# Switch_PCB_Schematic.net
KiCad netlist of a schematic drawn in Altium Designer
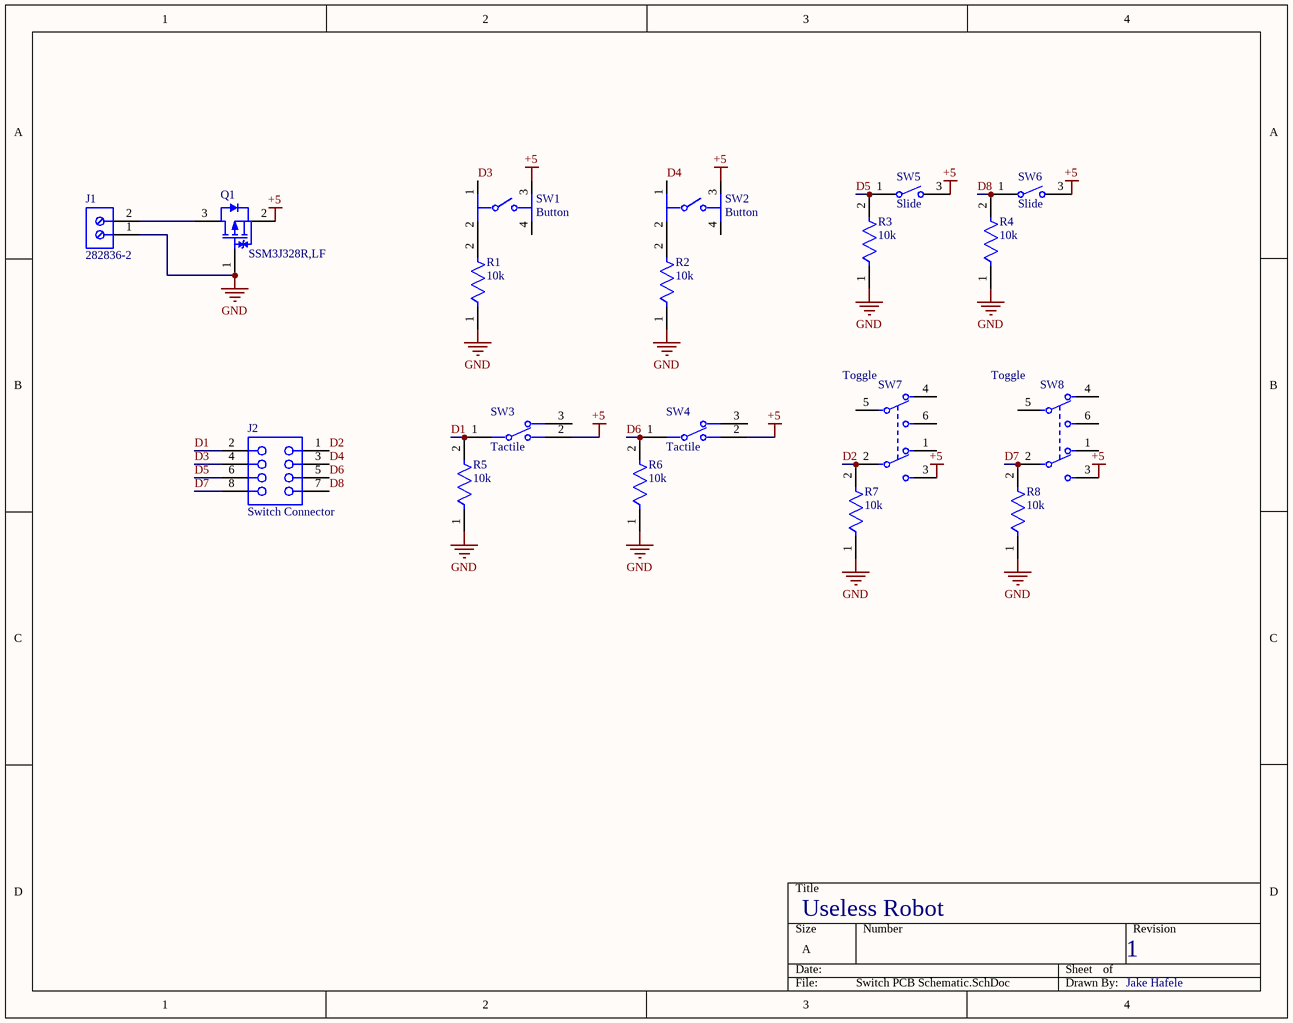
[diagram p0: Switch PCB Schematic.SchDoc]

(export (version "E")
  (design (tool "Eeschema 10.0.6"))
  (components
    (comp (ref "J1")
      (value "282836-2")
      (footprint "TECO-282836-2_V")
      (description "Female Header, Pitch 5 mm, 1 x 2 Position, Height 10 mm, Tail Length 3.5 mm, Rohs, Bulk")
      (fields (field (name "VOLTAGE") "300V") (field (name "MANUFACTURER") "TE Connectivity"))
      (libsource (lib "Altium Content Vault") (part "CN-1P-F-TB2"))
    )
    (comp (ref "J2")
      (value "Switch Connector")
      (footprint "SMTC-SSW-104-01-X-D")
      (description "SQ Post Socket, Through-hole, Vertical, -55 to 105 degC, 2.54mm Pitch, 8-Pin, Female, RoHS")
      (fields (field (name "PARTNUMBER") "SSW-104-01-T-D") (field (name "MANUFACTURER") "Samtec"))
      (libsource (lib "Altium Content Vault") (part "SMTC-SSW-104-X-X-D"))
    )
    (comp (ref "Q1")
      (value "SSM3J328R,LF")
      (footprint "TOSH-SOT-23F_V")
      (fields (field (name "MANUFACTURER") "Toshiba"))
      (libsource (lib "Altium Content Vault") (part "PEMOS-GSD-3_C"))
    )
    (comp (ref "R1")
      (value "10k")
      (footprint "FP-RT1206-MFG")
      (description "RES SMD 10K OHM 0.5% 1/4W 1206")
      (fields (field (name "MANUFACTURER PART NUMBER") "RT1206DRE0710KL") (field (name "TOLERANCE") "0.0001"))
      (libsource (lib "Altium Content Vault") (part "1029c3af85768c4190bb7ad29bc67b5"))
    )
    (comp (ref "R2")
      (value "10k")
      (footprint "FP-RT1206-MFG")
      (description "RES SMD 10K OHM 0.5% 1/4W 1206")
      (fields (field (name "MANUFACTURER PART NUMBER") "RT1206DRE0710KL") (field (name "TOLERANCE") "0.0001"))
      (libsource (lib "Altium Content Vault") (part "1029c3af85768c4190bb7ad29bc67b5"))
    )
    (comp (ref "R3")
      (value "10k")
      (footprint "FP-RT1206-MFG")
      (description "RES SMD 10K OHM 0.5% 1/4W 1206")
      (fields (field (name "MANUFACTURER PART NUMBER") "RT1206DRE0710KL") (field (name "TOLERANCE") "0.0001"))
      (libsource (lib "Altium Content Vault") (part "1029c3af85768c4190bb7ad29bc67b5"))
    )
    (comp (ref "R4")
      (value "10k")
      (footprint "FP-RT1206-MFG")
      (description "RES SMD 10K OHM 0.5% 1/4W 1206")
      (fields (field (name "MANUFACTURER PART NUMBER") "RT1206DRE0710KL") (field (name "TOLERANCE") "0.0001"))
      (libsource (lib "Altium Content Vault") (part "1029c3af85768c4190bb7ad29bc67b5"))
    )
    (comp (ref "R5")
      (value "10k")
      (footprint "FP-RT1206-MFG")
      (description "RES SMD 10K OHM 0.5% 1/4W 1206")
      (fields (field (name "MANUFACTURER PART NUMBER") "RT1206DRE0710KL") (field (name "TOLERANCE") "0.0001"))
      (libsource (lib "Altium Content Vault") (part "1029c3af85768c4190bb7ad29bc67b5"))
    )
    (comp (ref "R6")
      (value "10k")
      (footprint "FP-RT1206-MFG")
      (description "RES SMD 10K OHM 0.5% 1/4W 1206")
      (fields (field (name "MANUFACTURER PART NUMBER") "RT1206DRE0710KL") (field (name "TOLERANCE") "0.0001"))
      (libsource (lib "Altium Content Vault") (part "1029c3af85768c4190bb7ad29bc67b5"))
    )
    (comp (ref "R7")
      (value "10k")
      (footprint "FP-RT1206-MFG")
      (description "RES SMD 10K OHM 0.5% 1/4W 1206")
      (fields (field (name "MANUFACTURER PART NUMBER") "RT1206DRE0710KL") (field (name "TOLERANCE") "0.0001"))
      (libsource (lib "Altium Content Vault") (part "1029c3af85768c4190bb7ad29bc67b5"))
    )
    (comp (ref "R8")
      (value "10k")
      (footprint "FP-RT1206-MFG")
      (description "RES SMD 10K OHM 0.5% 1/4W 1206")
      (fields (field (name "MANUFACTURER PART NUMBER") "RT1206DRE0710KL") (field (name "TOLERANCE") "0.0001"))
      (libsource (lib "Altium Content Vault") (part "1029c3af85768c4190bb7ad29bc67b5"))
    )
    (comp (ref "SW1")
      (value "Button")
      (footprint "FP-1825910-2-0")
      (description "SWITCH TACTILE SPST-NO 0.05A 24V. Push button")
      (fields
        (field (name "OCTOPART") "https://octopart.com/1825910-2-te+connectivity-42270502")
        (field (name "MANUFACTURER") "TE")
      )
      (libsource (lib "Altium Content Vault") (part "b8895f3f4cefb76e1819d2863dba89b"))
    )
    (comp (ref "SW2")
      (value "Button")
      (footprint "FP-1825910-2-0")
      (description "SWITCH TACTILE SPST-NO 0.05A 24V. Push button")
      (fields
        (field (name "OCTOPART") "https://octopart.com/1825910-2-te+connectivity-42270502")
        (field (name "MANUFACTURER") "TE")
      )
      (libsource (lib "Altium Content Vault") (part "b8895f3f4cefb76e1819d2863dba89b"))
    )
    (comp (ref "SW3")
      (value "Tactile")
      (footprint "FP-SS-5GL2D-MFG")
      (description "SWITCH SNAP ACTION SPDT 5A 125V. Snap Action")
      (libsource (lib "Altium Content Vault") (part "2590abc66e99d69838a2e17c76decd2"))
    )
    (comp (ref "SW4")
      (value "Tactile")
      (footprint "FP-SS-5GL2D-MFG")
      (description "SWITCH SNAP ACTION SPDT 5A 125V. Snap Action")
      (libsource (lib "Altium Content Vault") (part "2590abc66e99d69838a2e17c76decd2"))
    )
    (comp (ref "SW5")
      (value "Slide")
      (footprint "CKCP-TS02CBE_V")
      (description "Tiny Slide Switch, SPST, 20 V, -30 to 85 degC, 2-Pin THD, RoHS, Bulk Slide Switch")
      (fields (field (name "MANUFACTURER") "C&K Components"))
      (libsource (lib "Altium Content Vault") (part "SW-SPST-2"))
    )
    (comp (ref "SW6")
      (value "Slide")
      (footprint "CKCP-TS02CBE_V")
      (description "Tiny Slide Switch, SPST, 20 V, -30 to 85 degC, 2-Pin THD, RoHS, Bulk Slide Switch")
      (fields (field (name "MANUFACTURER") "C&K Components"))
      (libsource (lib "Altium Content Vault") (part "SW-SPST-2"))
    )
    (comp (ref "SW7")
      (value "Toggle")
      (footprint "FP-100DP1T2B3M2QEH-MFG")
      (description "SWITCH TOGGLE NON ILLUMINATED. Double Pole Single Throw")
      (fields
        (field (name "MANUFACTURER") "E-Switch")
        (field (name "OCTOPART") "https://octopart.com/100dp1t2b3m2qeh-e-switch-7054946")
      )
      (libsource (lib "Altium Content Vault") (part "0cfc74b8a78428f8f812a73d8c28120"))
    )
    (comp (ref "SW8")
      (value "Toggle")
      (footprint "FP-100DP1T2B3M2QEH-MFG")
      (description "SWITCH TOGGLE NON ILLUMINATED. Double Pole Single Throw")
      (fields
        (field (name "MANUFACTURER") "E-Switch")
        (field (name "OCTOPART") "https://octopart.com/100dp1t2b3m2qeh-e-switch-7054946")
      )
      (libsource (lib "Altium Content Vault") (part "0cfc74b8a78428f8f812a73d8c28120"))
    )
  )
  (nets
    (net (code "1") (name "+5") (class "Default")
      (node (ref "Q1") (pin "2") (pinfunction "S_2") (pintype "passive"))
      (node (ref "SW1") (pin "3") (pinfunction "3_3") (pintype "passive"))
      (node (ref "SW2") (pin "3") (pinfunction "3_3") (pintype "passive"))
      (node (ref "SW3") (pin "2") (pinfunction "NO_2") (pintype "passive"))
      (node (ref "SW4") (pin "2") (pinfunction "NO_2") (pintype "passive"))
      (node (ref "SW5") (pin "3") (pinfunction "3_3") (pintype "passive"))
      (node (ref "SW6") (pin "3") (pinfunction "3_3") (pintype "passive"))
      (node (ref "SW7") (pin "3") (pinfunction "3_3") (pintype "passive"))
      (node (ref "SW8") (pin "3") (pinfunction "3_3") (pintype "passive"))
    )
    (net (code "2") (name "/D1") (class "Default")
      (node (ref "J2") (pin "2") (pinfunction "2_2") (pintype "passive"))
      (node (ref "R5") (pin "2") (pinfunction "2_2") (pintype "passive"))
      (node (ref "SW3") (pin "1") (pinfunction "COM_1") (pintype "passive"))
    )
    (net (code "3") (name "/D2") (class "Default")
      (node (ref "J2") (pin "1") (pinfunction "1_1") (pintype "passive"))
      (node (ref "R7") (pin "2") (pinfunction "2_2") (pintype "passive"))
      (node (ref "SW7") (pin "2") (pinfunction "2_2") (pintype "passive"))
    )
    (net (code "4") (name "/D3") (class "Default")
      (node (ref "J2") (pin "4") (pinfunction "4_4") (pintype "passive"))
      (node (ref "SW1") (pin "1") (pinfunction "1_1") (pintype "passive"))
    )
    (net (code "5") (name "/D4") (class "Default")
      (node (ref "J2") (pin "3") (pinfunction "3_3") (pintype "passive"))
      (node (ref "SW2") (pin "1") (pinfunction "1_1") (pintype "passive"))
    )
    (net (code "6") (name "/D5") (class "Default")
      (node (ref "J2") (pin "6") (pinfunction "6_6") (pintype "passive"))
      (node (ref "R3") (pin "2") (pinfunction "2_2") (pintype "passive"))
      (node (ref "SW5") (pin "1") (pinfunction "1_1") (pintype "passive"))
    )
    (net (code "7") (name "/D6") (class "Default")
      (node (ref "J2") (pin "5") (pinfunction "5_5") (pintype "passive"))
      (node (ref "R6") (pin "2") (pinfunction "2_2") (pintype "passive"))
      (node (ref "SW4") (pin "1") (pinfunction "COM_1") (pintype "passive"))
    )
    (net (code "8") (name "/D7") (class "Default")
      (node (ref "J2") (pin "8") (pinfunction "8_8") (pintype "passive"))
      (node (ref "R8") (pin "2") (pinfunction "2_2") (pintype "passive"))
      (node (ref "SW8") (pin "2") (pinfunction "2_2") (pintype "passive"))
    )
    (net (code "9") (name "/D8") (class "Default")
      (node (ref "J2") (pin "7") (pinfunction "7_7") (pintype "passive"))
      (node (ref "R4") (pin "2") (pinfunction "2_2") (pintype "passive"))
      (node (ref "SW6") (pin "1") (pinfunction "1_1") (pintype "passive"))
    )
    (net (code "10") (name "GND") (class "Default")
      (node (ref "J1") (pin "1") (pinfunction "1_1") (pintype "passive"))
      (node (ref "Q1") (pin "1") (pinfunction "G_1") (pintype "passive"))
      (node (ref "R1") (pin "1") (pinfunction "1_1") (pintype "passive"))
      (node (ref "R2") (pin "1") (pinfunction "1_1") (pintype "passive"))
      (node (ref "R3") (pin "1") (pinfunction "1_1") (pintype "passive"))
      (node (ref "R4") (pin "1") (pinfunction "1_1") (pintype "passive"))
      (node (ref "R5") (pin "1") (pinfunction "1_1") (pintype "passive"))
      (node (ref "R6") (pin "1") (pinfunction "1_1") (pintype "passive"))
      (node (ref "R7") (pin "1") (pinfunction "1_1") (pintype "passive"))
      (node (ref "R8") (pin "1") (pinfunction "1_1") (pintype "passive"))
    )
    (net (code "11") (name "Net-(Q1-D)") (class "Default")
      (node (ref "J1") (pin "2") (pinfunction "2_2") (pintype "passive"))
      (node (ref "Q1") (pin "3") (pinfunction "D_3") (pintype "passive"))
    )
    (net (code "12") (name "Net-(R1-Pad2)") (class "Default")
      (node (ref "R1") (pin "2") (pinfunction "2_2") (pintype "passive"))
      (node (ref "SW1") (pin "2") (pinfunction "2_2") (pintype "passive"))
    )
    (net (code "13") (name "Net-(R2-Pad2)") (class "Default")
      (node (ref "R2") (pin "2") (pinfunction "2_2") (pintype "passive"))
      (node (ref "SW2") (pin "2") (pinfunction "2_2") (pintype "passive"))
    )
    (net (code "14") (name "unconnected-(SW1-Pad4)") (class "Default")
      (node (ref "SW1") (pin "4") (pinfunction "4_4") (pintype "passive"))
    )
    (net (code "15") (name "unconnected-(SW2-Pad4)") (class "Default")
      (node (ref "SW2") (pin "4") (pinfunction "4_4") (pintype "passive"))
    )
    (net (code "16") (name "unconnected-(SW3-NC-Pad3)") (class "Default")
      (node (ref "SW3") (pin "3") (pinfunction "NC_3") (pintype "passive"))
    )
    (net (code "17") (name "unconnected-(SW4-NC-Pad3)") (class "Default")
      (node (ref "SW4") (pin "3") (pinfunction "NC_3") (pintype "passive"))
    )
    (net (code "18") (name "unconnected-(SW7-Pad1)") (class "Default")
      (node (ref "SW7") (pin "1") (pinfunction "1_1") (pintype "passive"))
    )
    (net (code "19") (name "unconnected-(SW7-Pad4)") (class "Default")
      (node (ref "SW7") (pin "4") (pinfunction "4_4") (pintype "passive"))
    )
    (net (code "20") (name "unconnected-(SW7-Pad5)") (class "Default")
      (node (ref "SW7") (pin "5") (pinfunction "5_5") (pintype "passive"))
    )
    (net (code "21") (name "unconnected-(SW7-Pad6)") (class "Default")
      (node (ref "SW7") (pin "6") (pinfunction "6_6") (pintype "passive"))
    )
    (net (code "22") (name "unconnected-(SW8-Pad1)") (class "Default")
      (node (ref "SW8") (pin "1") (pinfunction "1_1") (pintype "passive"))
    )
    (net (code "23") (name "unconnected-(SW8-Pad4)") (class "Default")
      (node (ref "SW8") (pin "4") (pinfunction "4_4") (pintype "passive"))
    )
    (net (code "24") (name "unconnected-(SW8-Pad5)") (class "Default")
      (node (ref "SW8") (pin "5") (pinfunction "5_5") (pintype "passive"))
    )
    (net (code "25") (name "unconnected-(SW8-Pad6)") (class "Default")
      (node (ref "SW8") (pin "6") (pinfunction "6_6") (pintype "passive"))
    )
  )
)
